# BandaiLights.net
KiCad netlist of a schematic drawn in EAGLE
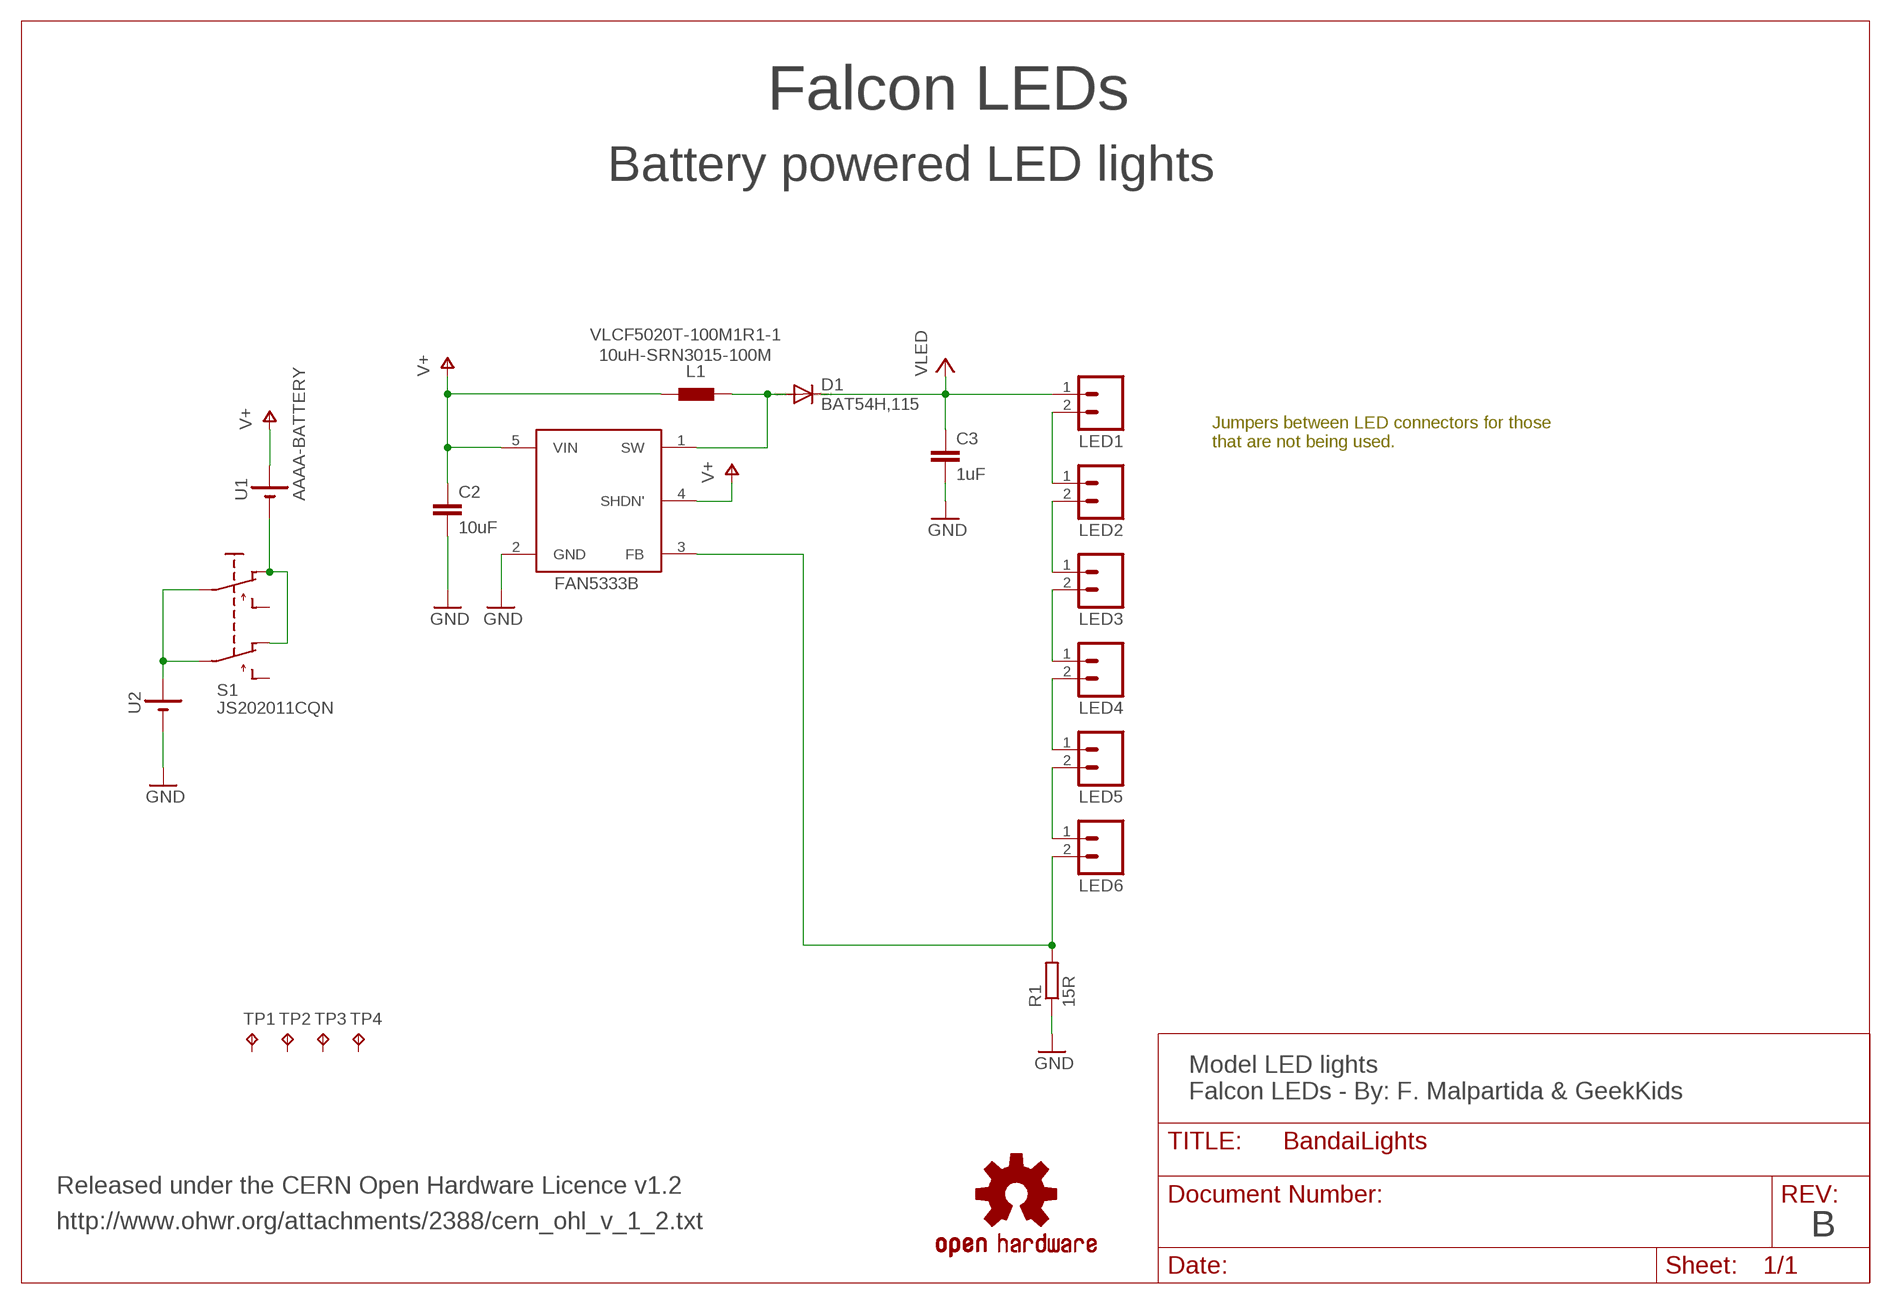
[diagram p0: schematic, sheet 1]

(export (version "E")
  (design (tool "Eeschema 10.0.6"))
  (components
    (comp (ref "C2")
      (value "10uF")
      (footprint "eagle-import:C1206")
      (libsource (lib "eagle-import") (part "C-EUC1206"))
    )
    (comp (ref "C3")
      (value "1uF")
      (footprint "eagle-import:C0805")
      (libsource (lib "eagle-import") (part "C-EUC0805"))
    )
    (comp (ref "D1")
      (value "BAT54H,115")
      (footprint "eagle-import:SOD123")
      (libsource (lib "eagle-import") (part "MBR0520LT"))
    )
    (comp (ref "L1")
      (value "10uH-SRN3015-100M")
      (footprint "eagle-import:LQH")
      (libsource (lib "eagle-import") (part "LQHXXSNLQH55DN"))
    )
    (comp (ref "LED1")
      (value "M02PTH")
      (footprint "eagle-import:1X02")
      (libsource (lib "eagle-import") (part "M02PTH"))
    )
    (comp (ref "LED2")
      (value "M02PTH")
      (footprint "eagle-import:1X02")
      (libsource (lib "eagle-import") (part "M02PTH"))
    )
    (comp (ref "LED3")
      (value "M02PTH")
      (footprint "eagle-import:1X02")
      (libsource (lib "eagle-import") (part "M02PTH"))
    )
    (comp (ref "LED4")
      (value "M02PTH")
      (footprint "eagle-import:1X02")
      (libsource (lib "eagle-import") (part "M02PTH"))
    )
    (comp (ref "LED5")
      (value "M02PTH")
      (footprint "eagle-import:1X02")
      (libsource (lib "eagle-import") (part "M02PTH"))
    )
    (comp (ref "LED6")
      (value "M02PTH")
      (footprint "eagle-import:1X02")
      (libsource (lib "eagle-import") (part "M02PTH"))
    )
    (comp (ref "Q1")
      (value "FAN5333B")
      (footprint "eagle-import:SOT23-5")
      (libsource (lib "eagle-import") (part "CAT4238"))
    )
    (comp (ref "R1")
      (value "15R")
      (footprint "eagle-import:M0805")
      (libsource (lib "eagle-import") (part "R-EU_M0805"))
    )
    (comp (ref "S1")
      (value "JS202011CQN")
      (footprint "eagle-import:SWITCH-JS202011")
      (libsource (lib "eagle-import") (part "MINI_SWITCH"))
    )
    (comp (ref "TP1")
      (value "TPB1,27")
      (footprint "eagle-import:B1,27")
      (libsource (lib "eagle-import") (part "TPB1,27"))
    )
    (comp (ref "TP2")
      (value "TPB1,27")
      (footprint "eagle-import:B1,27")
      (libsource (lib "eagle-import") (part "TPB1,27"))
    )
    (comp (ref "TP3")
      (value "TPB1,27")
      (footprint "eagle-import:B1,27")
      (libsource (lib "eagle-import") (part "TPB1,27"))
    )
    (comp (ref "TP4")
      (value "TPB1,27")
      (footprint "eagle-import:B1,27")
      (libsource (lib "eagle-import") (part "TPB1,27"))
    )
    (comp (ref "U$4")
      (value "SPARKFUN_OSHW-LOGOM")
      (footprint "eagle-import:SPARKFUN_OSHW-LOGO-M")
      (libsource (lib "eagle-import") (part "SPARKFUN_OSHW-LOGOM"))
    )
    (comp (ref "U1")
      (value "AAAA-BATTERY")
      (footprint "eagle-import:51-AAAA")
      (libsource (lib "eagle-import") (part "AAAA-BATTERY"))
    )
    (comp (ref "U2")
      (value "AAAA-BATTERY")
      (footprint "eagle-import:51-AAAA")
      (libsource (lib "eagle-import") (part "AAAA-BATTERY"))
    )
  )
  (nets
    (net (code "1") (name "GND") (class "Default")
      (node (ref "C2") (pin "2") (pinfunction "2_2") (pintype "passive"))
      (node (ref "C3") (pin "2") (pinfunction "2_2") (pintype "passive"))
      (node (ref "Q1") (pin "2") (pinfunction "GND_2") (pintype "bidirectional"))
      (node (ref "R1") (pin "1") (pinfunction "1_1") (pintype "passive"))
      (node (ref "U2") (pin "P3") (pinfunction "-_P3") (pintype "passive"))
      (node (ref "U2") (pin "P4") (pinfunction "-_P4") (pintype "passive"))
    )
    (net (code "2") (name "Net-(LED1-Pad2)") (class "Default")
      (node (ref "LED1") (pin "2") (pinfunction "2_2") (pintype "passive"))
      (node (ref "LED2") (pin "1") (pinfunction "1_1") (pintype "passive"))
    )
    (net (code "3") (name "Net-(LED2-Pad2)") (class "Default")
      (node (ref "LED2") (pin "2") (pinfunction "2_2") (pintype "passive"))
      (node (ref "LED3") (pin "1") (pinfunction "1_1") (pintype "passive"))
    )
    (net (code "4") (name "Net-(LED3-Pad2)") (class "Default")
      (node (ref "LED3") (pin "2") (pinfunction "2_2") (pintype "passive"))
      (node (ref "LED4") (pin "1") (pinfunction "1_1") (pintype "passive"))
    )
    (net (code "5") (name "Net-(LED4-Pad2)") (class "Default")
      (node (ref "LED4") (pin "2") (pinfunction "2_2") (pintype "passive"))
      (node (ref "LED5") (pin "1") (pinfunction "1_1") (pintype "passive"))
    )
    (net (code "6") (name "Net-(LED5-Pad2)") (class "Default")
      (node (ref "LED5") (pin "2") (pinfunction "2_2") (pintype "passive"))
      (node (ref "LED6") (pin "1") (pinfunction "1_1") (pintype "passive"))
    )
    (net (code "7") (name "Net-(Q1-FB)") (class "Default")
      (node (ref "LED6") (pin "2") (pinfunction "2_2") (pintype "passive"))
      (node (ref "Q1") (pin "3") (pinfunction "FB_3") (pintype "bidirectional"))
      (node (ref "R1") (pin "2") (pinfunction "2_2") (pintype "passive"))
    )
    (net (code "8") (name "Net-(Q1-SW)") (class "Default")
      (node (ref "D1") (pin "A") (pinfunction "A_A") (pintype "passive"))
      (node (ref "L1") (pin "2") (pinfunction "2_2") (pintype "passive"))
      (node (ref "Q1") (pin "1") (pinfunction "SW_1") (pintype "bidirectional"))
    )
    (net (code "9") (name "Net-(S1-O)") (class "Default")
      (node (ref "S1") (pin "P1") (pinfunction "O_P1") (pintype "passive"))
      (node (ref "S1") (pin "P4") (pinfunction "O1_P4") (pintype "passive"))
      (node (ref "U1") (pin "P3") (pinfunction "-_P3") (pintype "passive"))
      (node (ref "U1") (pin "P4") (pinfunction "-_P4") (pintype "passive"))
    )
    (net (code "10") (name "Net-(S1-P)") (class "Default")
      (node (ref "S1") (pin "P2") (pinfunction "P_P2") (pintype "passive"))
      (node (ref "S1") (pin "P5") (pinfunction "P1_P5") (pintype "passive"))
      (node (ref "U2") (pin "P1") (pinfunction "+_P1") (pintype "passive"))
      (node (ref "U2") (pin "P2") (pinfunction "+_P2") (pintype "passive"))
    )
    (net (code "11") (name "V+") (class "Default")
      (node (ref "C2") (pin "1") (pinfunction "1_1") (pintype "passive"))
      (node (ref "L1") (pin "1") (pinfunction "1_1") (pintype "passive"))
      (node (ref "Q1") (pin "4") (pinfunction "SHDN'_4") (pintype "bidirectional"))
      (node (ref "Q1") (pin "5") (pinfunction "VIN_5") (pintype "bidirectional"))
      (node (ref "U1") (pin "P1") (pinfunction "+_P1") (pintype "passive"))
      (node (ref "U1") (pin "P2") (pinfunction "+_P2") (pintype "passive"))
    )
    (net (code "12") (name "VLED") (class "Default")
      (node (ref "C3") (pin "1") (pinfunction "1_1") (pintype "passive"))
      (node (ref "D1") (pin "C") (pinfunction "C_C") (pintype "passive"))
      (node (ref "LED1") (pin "1") (pinfunction "1_1") (pintype "passive"))
    )
    (net (code "13") (name "unconnected-(S1-S-PadP3)") (class "Default")
      (node (ref "S1") (pin "P3") (pinfunction "S_P3") (pintype "passive"))
    )
    (net (code "14") (name "unconnected-(S1-S1-PadP6)") (class "Default")
      (node (ref "S1") (pin "P6") (pinfunction "S1_P6") (pintype "passive"))
    )
    (net (code "15") (name "unconnected-(TP1-PadTP)") (class "Default")
      (node (ref "TP1") (pin "TP") (pinfunction "TP_TP") (pintype "input"))
    )
    (net (code "16") (name "unconnected-(TP2-PadTP)") (class "Default")
      (node (ref "TP2") (pin "TP") (pinfunction "TP_TP") (pintype "input"))
    )
    (net (code "17") (name "unconnected-(TP3-PadTP)") (class "Default")
      (node (ref "TP3") (pin "TP") (pinfunction "TP_TP") (pintype "input"))
    )
    (net (code "18") (name "unconnected-(TP4-PadTP)") (class "Default")
      (node (ref "TP4") (pin "TP") (pinfunction "TP_TP") (pintype "input"))
    )
  )
)
